# Battery.net
KiCad netlist of a schematic drawn in Altium Designer
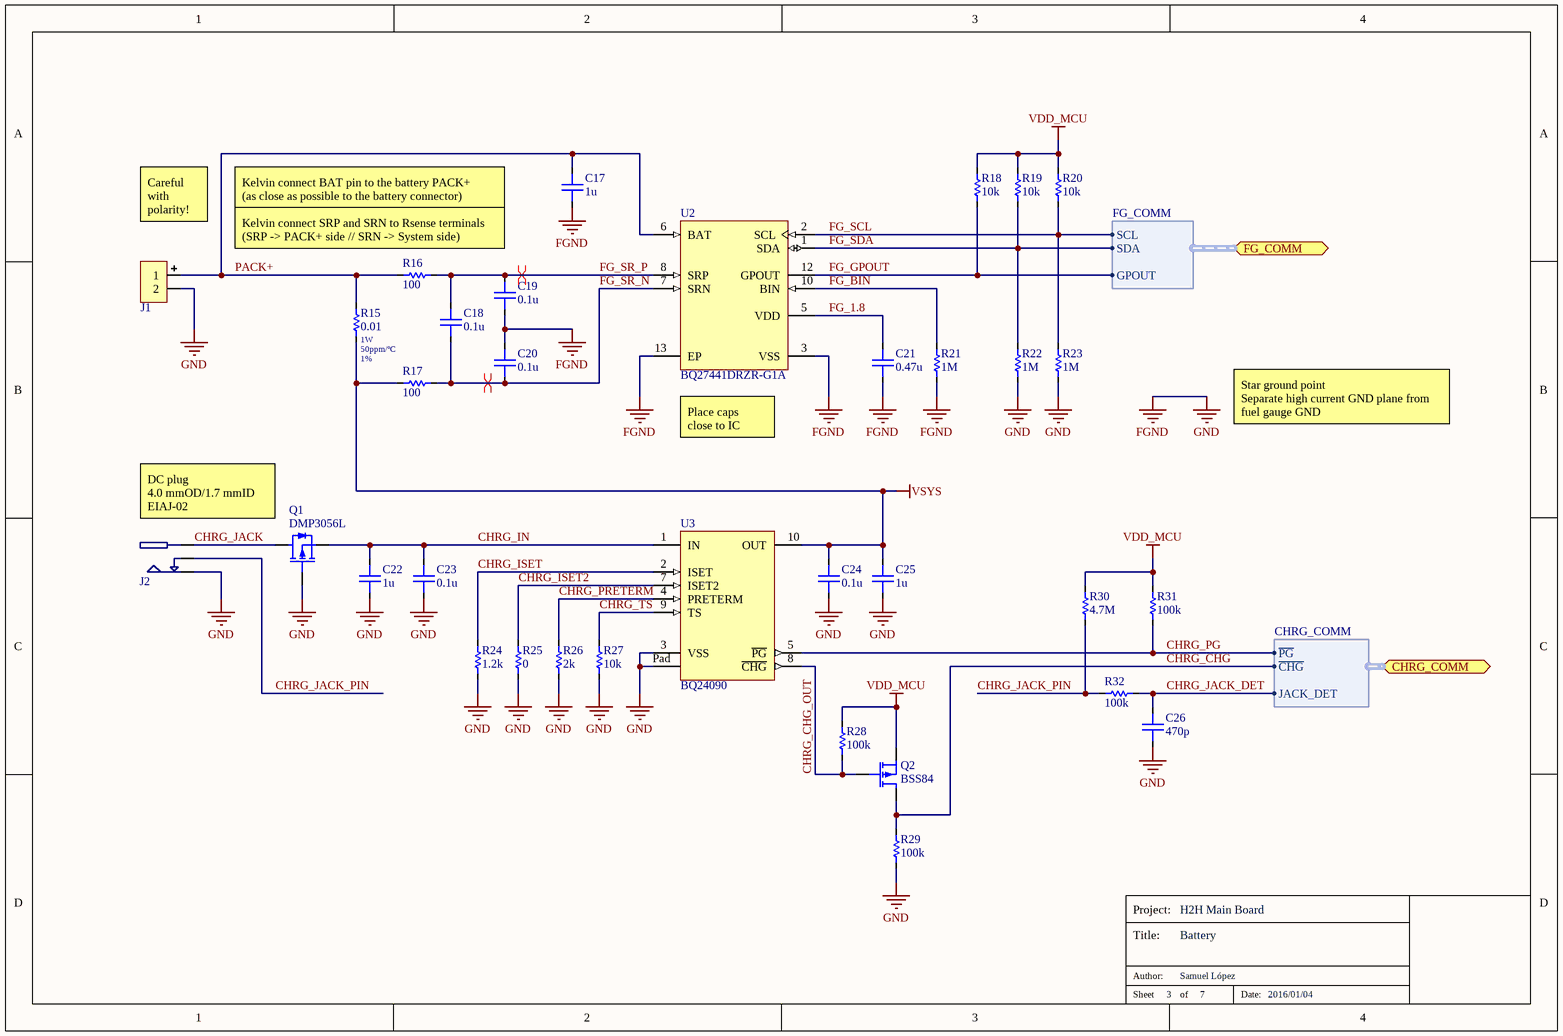
[diagram p0: Battery.SchDoc]

(export (version "E")
  (design (tool "Eeschema 10.0.6"))
  (components
    (comp (ref "C17")
      (value "1u")
      (footprint "C0603")
      (description "Capacitor")
      (libsource (lib "Misc") (part "Capacitor"))
    )
    (comp (ref "C18")
      (value "0.1u")
      (footprint "C0603")
      (description "Capacitor")
      (libsource (lib "Misc") (part "Capacitor"))
    )
    (comp (ref "C19")
      (value "0.1u")
      (footprint "C0603")
      (description "Capacitor")
      (libsource (lib "Misc") (part "Capacitor"))
    )
    (comp (ref "C20")
      (value "0.1u")
      (footprint "C0603")
      (description "Capacitor")
      (libsource (lib "Misc") (part "Capacitor"))
    )
    (comp (ref "C21")
      (value "0.47u")
      (footprint "C0603")
      (description "Capacitor")
      (libsource (lib "Misc") (part "Capacitor"))
    )
    (comp (ref "C22")
      (value "1u")
      (footprint "C0603")
      (description "Capacitor")
      (libsource (lib "Misc") (part "Capacitor"))
    )
    (comp (ref "C23")
      (value "0.1u")
      (footprint "C0603")
      (description "Capacitor")
      (libsource (lib "Misc") (part "Capacitor"))
    )
    (comp (ref "C24")
      (value "0.1u")
      (footprint "C0603")
      (description "Capacitor")
      (libsource (lib "Misc") (part "Capacitor"))
    )
    (comp (ref "C25")
      (value "1u")
      (footprint "C0603")
      (description "Capacitor")
      (libsource (lib "Misc") (part "Capacitor"))
    )
    (comp (ref "C26")
      (value "470p")
      (footprint "C0603")
      (description "Capacitor")
      (libsource (lib "Misc") (part "Capacitor"))
    )
    (comp (ref "J1")
      (value "JST PH 2 Pin")
      (footprint "S2B-PH-K-S")
      (description "Conn - Battery, Male, 2 Pin, PCB, Right Angle")
      (libsource (lib "Conn") (part "S2B-PH-K-S"))
    )
    (comp (ref "J2")
      (value "PJ-018H-SMT")
      (footprint "PJ-018H-SMT")
      (description "Conn - DC Power Plug - 4.0 mmOD / 1.7 mmID")
      (libsource (lib "Conn") (part "PJ-018H-SMT"))
    )
    (comp (ref "Q1")
      (value "DMP3056L")
      (footprint "DMP3056L")
      (description "Transistor - MOSFET, P-Channel, 30V, 4.3A")
      (libsource (lib "H2H") (part "DMP3056L"))
    )
    (comp (ref "Q2")
      (value "BSS84")
      (footprint "BSS84")
      (description "Transistor - MOSFET, P-Channel, 50V, 130mA")
      (libsource (lib "H2H") (part "BSS84"))
    )
    (comp (ref "R15")
      (value "0.01")
      (footprint "R1206")
      (description "Resistor")
      (fields
        (field (name "POWER") "1W")
        (field (name "TOLERANCE") "1%")
        (field (name "TEMP. COEF.") "50ppm/ºC")
      )
      (libsource (lib "Misc") (part "Resistor"))
    )
    (comp (ref "R16")
      (value "100")
      (footprint "R0603")
      (description "Resistor")
      (libsource (lib "Misc") (part "Resistor"))
    )
    (comp (ref "R17")
      (value "100")
      (footprint "R0603")
      (description "Resistor")
      (libsource (lib "Misc") (part "Resistor"))
    )
    (comp (ref "R18")
      (value "10k")
      (footprint "R0603")
      (description "Resistor")
      (libsource (lib "Misc") (part "Resistor"))
    )
    (comp (ref "R19")
      (value "10k")
      (footprint "R0603")
      (description "Resistor")
      (libsource (lib "Misc") (part "Resistor"))
    )
    (comp (ref "R20")
      (value "10k")
      (footprint "R0603")
      (description "Resistor")
      (libsource (lib "Misc") (part "Resistor"))
    )
    (comp (ref "R21")
      (value "1M")
      (footprint "R0603")
      (description "Resistor")
      (libsource (lib "Misc") (part "Resistor"))
    )
    (comp (ref "R22")
      (value "1M")
      (footprint "R0603")
      (description "Resistor")
      (libsource (lib "Misc") (part "Resistor"))
    )
    (comp (ref "R23")
      (value "1M")
      (footprint "R0603")
      (description "Resistor")
      (libsource (lib "Misc") (part "Resistor"))
    )
    (comp (ref "R24")
      (value "1.2k")
      (footprint "R0603")
      (description "Resistor")
      (libsource (lib "Misc") (part "Resistor"))
    )
    (comp (ref "R25")
      (value "0")
      (footprint "R0603")
      (description "Resistor")
      (libsource (lib "Misc") (part "Resistor"))
    )
    (comp (ref "R26")
      (value "2k")
      (footprint "R0603")
      (description "Resistor")
      (libsource (lib "Misc") (part "Resistor"))
    )
    (comp (ref "R27")
      (value "10k")
      (footprint "R0603")
      (description "Resistor")
      (libsource (lib "Misc") (part "Resistor"))
    )
    (comp (ref "R28")
      (value "100k")
      (footprint "R0603")
      (description "Resistor")
      (libsource (lib "Misc") (part "Resistor"))
    )
    (comp (ref "R29")
      (value "100k")
      (footprint "R0603")
      (description "Resistor")
      (libsource (lib "Misc") (part "Resistor"))
    )
    (comp (ref "R30")
      (value "4.7M")
      (footprint "R0603")
      (description "Resistor")
      (libsource (lib "Misc") (part "Resistor"))
    )
    (comp (ref "R31")
      (value "100k")
      (footprint "R0603")
      (description "Resistor")
      (libsource (lib "Misc") (part "Resistor"))
    )
    (comp (ref "R32")
      (value "100k")
      (footprint "R0603")
      (description "Resistor")
      (libsource (lib "Misc") (part "Resistor"))
    )
    (comp (ref "U2")
      (value "BQ27441DRZR-G1A")
      (footprint "BQ27441DRZx-G1A")
      (description "IC - Fuel Gauge, System-Side Impedance Track")
      (fields (field (name "PARTNUMBER") "BQ27410DRZR-G1A") (field (name "MANUFACTURER") "Texas Instruments"))
      (libsource (lib "H2H") (part "BQ27441DRZR-G1A"))
    )
    (comp (ref "U3")
      (value "BQ24090")
      (footprint "BQ24090")
      (description "IC - Battery Charger, Single Cell Li-Ion/LiPo, 1A")
      (libsource (lib "H2H") (part "BQ24090"))
    )
  )
  (nets
    (net (code "3") (name "/CHRG_CHG") (class "Default")
      (node (ref "Q2") (pin "3") (pinfunction "D_3") (pintype "passive"))
      (node (ref "R29") (pin "1") (pinfunction "1_1") (pintype "passive"))
    )
    (net (code "4") (name "/CHRG_CHG_OUT") (class "Default")
      (node (ref "Q2") (pin "1") (pinfunction "G_1") (pintype "passive"))
      (node (ref "R28") (pin "2") (pinfunction "2_2") (pintype "passive"))
      (node (ref "U3") (pin "8") (pinfunction "~{CHG}_8") (pintype "output"))
    )
    (net (code "5") (name "/CHRG_IN") (class "Default")
      (node (ref "C22") (pin "2") (pinfunction "2_2") (pintype "passive"))
      (node (ref "C23") (pin "2") (pinfunction "2_2") (pintype "passive"))
      (node (ref "Q1") (pin "2") (pinfunction "S_2") (pintype "passive"))
      (node (ref "U3") (pin "1") (pinfunction "IN_1") (pintype "power_in"))
    )
    (net (code "6") (name "/CHRG_ISET") (class "Default")
      (node (ref "R24") (pin "1") (pinfunction "1_1") (pintype "passive"))
      (node (ref "U3") (pin "2") (pinfunction "ISET_2") (pintype "input"))
    )
    (net (code "7") (name "/CHRG_ISET2") (class "Default")
      (node (ref "R25") (pin "1") (pinfunction "1_1") (pintype "passive"))
      (node (ref "U3") (pin "7") (pinfunction "ISET2_7") (pintype "input"))
    )
    (net (code "8") (name "/CHRG_JACK") (class "Default")
      (node (ref "J2") (pin "1") (pinfunction "1_1") (pintype "passive"))
      (node (ref "Q1") (pin "3") (pinfunction "D_3") (pintype "passive"))
    )
    (net (code "9") (name "/CHRG_JACK_DET") (class "Default")
      (node (ref "C26") (pin "2") (pinfunction "2_2") (pintype "passive"))
      (node (ref "R32") (pin "1") (pinfunction "1_1") (pintype "passive"))
    )
    (net (code "10") (name "/CHRG_JACK_PIN") (class "Default")
      (node (ref "J2") (pin "3") (pinfunction "3_3") (pintype "passive"))
      (node (ref "R30") (pin "2") (pinfunction "2_2") (pintype "passive"))
      (node (ref "R32") (pin "2") (pinfunction "2_2") (pintype "passive"))
    )
    (net (code "11") (name "/CHRG_PG") (class "Default")
      (node (ref "R31") (pin "2") (pinfunction "2_2") (pintype "passive"))
      (node (ref "U3") (pin "5") (pinfunction "~{PG}_5") (pintype "output"))
    )
    (net (code "12") (name "/CHRG_PRETERM") (class "Default")
      (node (ref "R26") (pin "1") (pinfunction "1_1") (pintype "passive"))
      (node (ref "U3") (pin "4") (pinfunction "PRETERM_4") (pintype "input"))
    )
    (net (code "13") (name "/CHRG_TS") (class "Default")
      (node (ref "R27") (pin "1") (pinfunction "1_1") (pintype "passive"))
      (node (ref "U3") (pin "9") (pinfunction "TS_9") (pintype "input"))
    )
    (net (code "14") (name "/FG_1.8") (class "Default")
      (node (ref "C21") (pin "2") (pinfunction "2_2") (pintype "passive"))
      (node (ref "U2") (pin "5") (pinfunction "VDD_5") (pintype "power_in"))
    )
    (net (code "15") (name "/FG_BIN") (class "Default")
      (node (ref "R21") (pin "1") (pinfunction "1_1") (pintype "passive"))
      (node (ref "U2") (pin "10") (pinfunction "BIN_10") (pintype "input"))
    )
    (net (code "16") (name "/FG_GPOUT") (class "Default")
      (node (ref "R18") (pin "2") (pinfunction "2_2") (pintype "passive"))
      (node (ref "U2") (pin "12") (pinfunction "GPOUT_12") (pintype "open_collector"))
    )
    (net (code "17") (name "/FG_SCL") (class "Default")
      (node (ref "R20") (pin "2") (pinfunction "2_2") (pintype "passive"))
      (node (ref "R23") (pin "1") (pinfunction "1_1") (pintype "passive"))
      (node (ref "U2") (pin "2") (pinfunction "SCL_2") (pintype "input"))
    )
    (net (code "18") (name "/FG_SDA") (class "Default")
      (node (ref "R19") (pin "2") (pinfunction "2_2") (pintype "passive"))
      (node (ref "R22") (pin "1") (pinfunction "1_1") (pintype "passive"))
      (node (ref "U2") (pin "1") (pinfunction "SDA_1") (pintype "bidirectional"))
    )
    (net (code "19") (name "/FG_SR_N") (class "Default")
      (node (ref "C18") (pin "1") (pinfunction "1_1") (pintype "passive"))
      (node (ref "C20") (pin "1") (pinfunction "1_1") (pintype "passive"))
      (node (ref "R17") (pin "2") (pinfunction "2_2") (pintype "passive"))
      (node (ref "U2") (pin "7") (pinfunction "SRN_7") (pintype "input"))
    )
    (net (code "20") (name "/FG_SR_P") (class "Default")
      (node (ref "C18") (pin "2") (pinfunction "2_2") (pintype "passive"))
      (node (ref "C19") (pin "2") (pinfunction "2_2") (pintype "passive"))
      (node (ref "R16") (pin "2") (pinfunction "2_2") (pintype "passive"))
      (node (ref "U2") (pin "8") (pinfunction "SRP_8") (pintype "input"))
    )
    (net (code "21") (name "/PACK+") (class "Default")
      (node (ref "C17") (pin "2") (pinfunction "2_2") (pintype "passive"))
      (node (ref "J1") (pin "1") (pinfunction "1_1") (pintype "passive"))
      (node (ref "R15") (pin "1") (pinfunction "1_1") (pintype "passive"))
      (node (ref "R16") (pin "1") (pinfunction "1_1") (pintype "passive"))
      (node (ref "U2") (pin "6") (pinfunction "BAT_6") (pintype "input"))
    )
    (net (code "24") (name "FGND") (class "Default")
      (node (ref "C17") (pin "1") (pinfunction "1_1") (pintype "passive"))
      (node (ref "C19") (pin "1") (pinfunction "1_1") (pintype "passive"))
      (node (ref "C20") (pin "2") (pinfunction "2_2") (pintype "passive"))
      (node (ref "C21") (pin "1") (pinfunction "1_1") (pintype "passive"))
      (node (ref "C22") (pin "1") (pinfunction "1_1") (pintype "passive"))
      (node (ref "C23") (pin "1") (pinfunction "1_1") (pintype "passive"))
      (node (ref "C24") (pin "1") (pinfunction "1_1") (pintype "passive"))
      (node (ref "C25") (pin "1") (pinfunction "1_1") (pintype "passive"))
      (node (ref "C26") (pin "1") (pinfunction "1_1") (pintype "passive"))
      (node (ref "J1") (pin "2") (pinfunction "2_2") (pintype "passive"))
      (node (ref "J2") (pin "2") (pinfunction "2_2") (pintype "passive"))
      (node (ref "Q1") (pin "1") (pinfunction "G_1") (pintype "passive"))
      (node (ref "R21") (pin "2") (pinfunction "2_2") (pintype "passive"))
      (node (ref "R22") (pin "2") (pinfunction "2_2") (pintype "passive"))
      (node (ref "R23") (pin "2") (pinfunction "2_2") (pintype "passive"))
      (node (ref "R24") (pin "2") (pinfunction "2_2") (pintype "passive"))
      (node (ref "R25") (pin "2") (pinfunction "2_2") (pintype "passive"))
      (node (ref "R26") (pin "2") (pinfunction "2_2") (pintype "passive"))
      (node (ref "R27") (pin "2") (pinfunction "2_2") (pintype "passive"))
      (node (ref "R29") (pin "2") (pinfunction "2_2") (pintype "passive"))
      (node (ref "U2") (pin "13") (pinfunction "EP_13") (pintype "passive"))
      (node (ref "U2") (pin "3") (pinfunction "VSS_3") (pintype "power_in"))
      (node (ref "U3") (pin "3") (pinfunction "VSS_3") (pintype "power_in"))
      (node (ref "U3") (pin "Pad") (pinfunction "Thermal_Pad") (pintype "passive"))
    )
    (net (code "25") (name "VDD_MCU") (class "Default")
      (node (ref "Q2") (pin "2") (pinfunction "S_2") (pintype "passive"))
      (node (ref "R18") (pin "1") (pinfunction "1_1") (pintype "passive"))
      (node (ref "R19") (pin "1") (pinfunction "1_1") (pintype "passive"))
      (node (ref "R20") (pin "1") (pinfunction "1_1") (pintype "passive"))
      (node (ref "R28") (pin "1") (pinfunction "1_1") (pintype "passive"))
      (node (ref "R30") (pin "1") (pinfunction "1_1") (pintype "passive"))
      (node (ref "R31") (pin "1") (pinfunction "1_1") (pintype "passive"))
    )
    (net (code "26") (name "VSYS") (class "Default")
      (node (ref "C24") (pin "2") (pinfunction "2_2") (pintype "passive"))
      (node (ref "C25") (pin "2") (pinfunction "2_2") (pintype "passive"))
      (node (ref "R15") (pin "2") (pinfunction "2_2") (pintype "passive"))
      (node (ref "R17") (pin "1") (pinfunction "1_1") (pintype "passive"))
      (node (ref "U3") (pin "10") (pinfunction "OUT_10") (pintype "power_in"))
    )
  )
)
